# ac-adapter.net
KiCad netlist of a schematic drawn in EAGLE
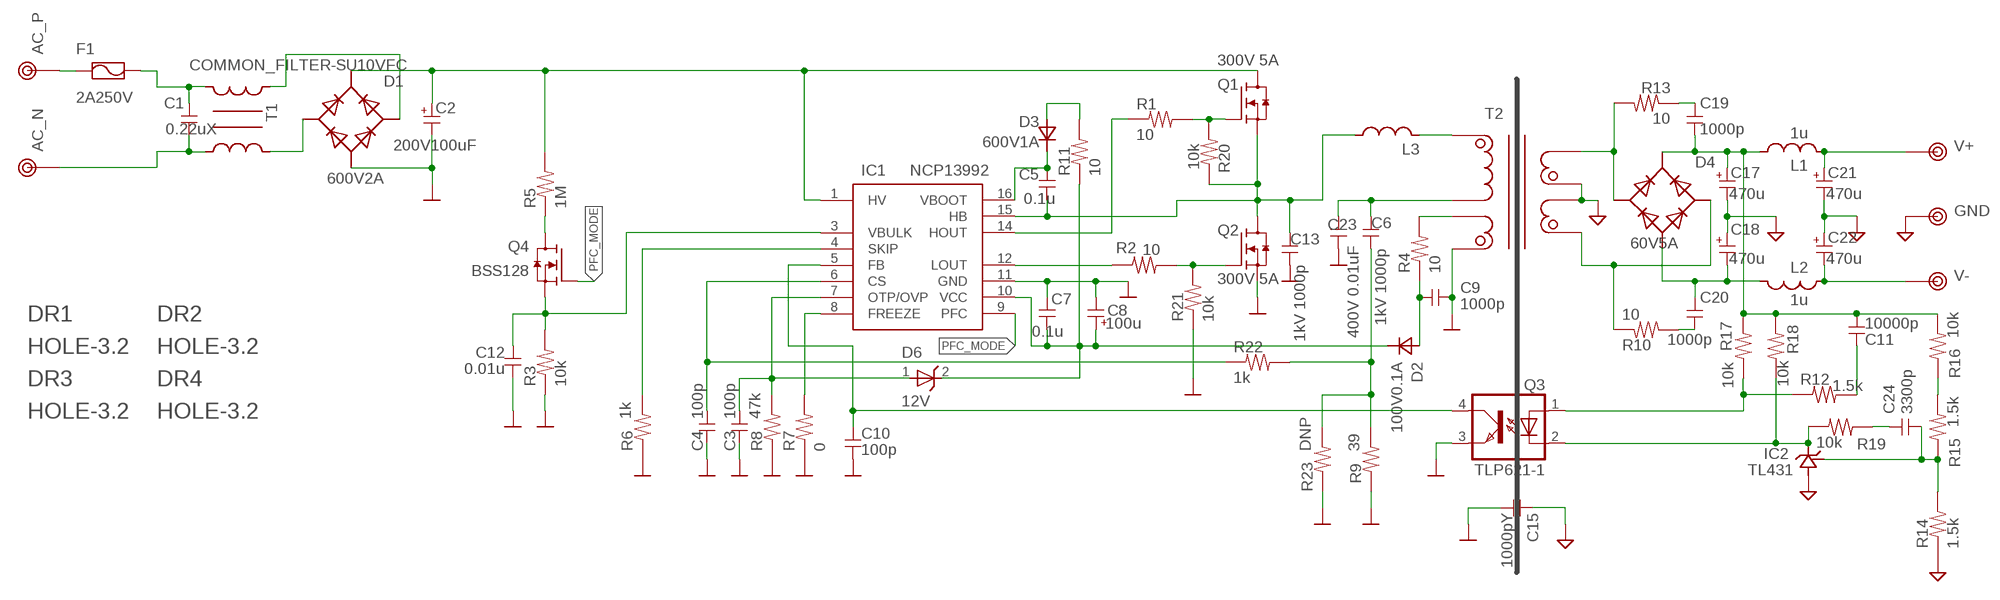
[diagram p0: schematic, sheet 1]

(export (version "E")
  (design (tool "Eeschema 10.0.6"))
  (components
    (comp (ref "C1")
      (value "0.22uX")
      (footprint "eagle-import:X-CAPACITER")
      (libsource (lib "eagle-import") (part "C-X"))
    )
    (comp (ref "C2")
      (value "200V100uF")
      (footprint "eagle-import:E5-16A2")
      (libsource (lib "eagle-import") (part "CPOLE7.5-16A2"))
    )
    (comp (ref "C3")
      (value "100p")
      (footprint "eagle-import:1608")
      (libsource (lib "eagle-import") (part "C-1608"))
    )
    (comp (ref "C4")
      (value "100p")
      (footprint "eagle-import:1608")
      (libsource (lib "eagle-import") (part "C-1608"))
    )
    (comp (ref "C5")
      (value "0.1u")
      (footprint "eagle-import:1608")
      (libsource (lib "eagle-import") (part "C-1608"))
    )
    (comp (ref "C6")
      (value "1kV 1000p")
      (footprint "eagle-import:C050")
      (libsource (lib "eagle-import") (part "C-5"))
    )
    (comp (ref "C7")
      (value "0.1u")
      (footprint "eagle-import:1608")
      (libsource (lib "eagle-import") (part "C-1608"))
    )
    (comp (ref "C8")
      (value "100u")
      (footprint "eagle-import:E2.5-6.5")
      (libsource (lib "eagle-import") (part "CPOLE2.5-6.5"))
    )
    (comp (ref "C9")
      (value "1000p")
      (footprint "eagle-import:1608")
      (libsource (lib "eagle-import") (part "C-1608"))
    )
    (comp (ref "C10")
      (value "100p")
      (footprint "eagle-import:1608")
      (libsource (lib "eagle-import") (part "C-1608"))
    )
    (comp (ref "C11")
      (value "10000p")
      (footprint "eagle-import:1608")
      (libsource (lib "eagle-import") (part "C-1608"))
    )
    (comp (ref "C12")
      (value "0.01u")
      (footprint "eagle-import:1608")
      (libsource (lib "eagle-import") (part "C-1608"))
    )
    (comp (ref "C13")
      (value "1kV 1000p")
      (footprint "eagle-import:C050")
      (libsource (lib "eagle-import") (part "C-5"))
    )
    (comp (ref "C15")
      (value "1000pY")
      (footprint "eagle-import:Y-CAPACITER")
      (libsource (lib "eagle-import") (part "C-Y"))
    )
    (comp (ref "C17")
      (value "470u")
      (footprint "eagle-import:E5-10")
      (libsource (lib "eagle-import") (part "CPOLE5-10"))
    )
    (comp (ref "C18")
      (value "470u")
      (footprint "eagle-import:E5-10")
      (libsource (lib "eagle-import") (part "CPOLE5-10"))
    )
    (comp (ref "C19")
      (value "1000p")
      (footprint "eagle-import:1608")
      (libsource (lib "eagle-import") (part "C-1608"))
    )
    (comp (ref "C20")
      (value "1000p")
      (footprint "eagle-import:1608")
      (libsource (lib "eagle-import") (part "C-1608"))
    )
    (comp (ref "C21")
      (value "470u")
      (footprint "eagle-import:E5-10")
      (libsource (lib "eagle-import") (part "CPOLE5-10"))
    )
    (comp (ref "C22")
      (value "470u")
      (footprint "eagle-import:E5-10")
      (libsource (lib "eagle-import") (part "CPOLE5-10"))
    )
    (comp (ref "C23")
      (value "400V 0.01uF")
      (footprint "eagle-import:C125")
      (libsource (lib "eagle-import") (part "C-12.5"))
    )
    (comp (ref "C24")
      (value "3300p")
      (footprint "eagle-import:1608")
      (libsource (lib "eagle-import") (part "C-1608"))
    )
    (comp (ref "D1")
      (value "600V2A")
      (footprint "eagle-import:GBU8A")
      (libsource (lib "eagle-import") (part "DIODE4-GBU8A"))
    )
    (comp (ref "D2")
      (value "100V0.1A")
      (footprint "eagle-import:SOD123")
      (libsource (lib "eagle-import") (part "DIODE-1N4148W"))
    )
    (comp (ref "D3")
      (value "600V1A")
      (footprint "eagle-import:D0204_7")
      (libsource (lib "eagle-import") (part "DIODE-7"))
    )
    (comp (ref "D4")
      (value "60V5A")
      (footprint "eagle-import:RBA-406")
      (libsource (lib "eagle-import") (part "DIODE4-RBA406B"))
    )
    (comp (ref "D6")
      (value "12V")
      (footprint "eagle-import:SOD123")
      (libsource (lib "eagle-import") (part "ZENER-SMD"))
    )
    (comp (ref "DR1")
      (value "HOLE-3.2")
      (footprint "eagle-import:HOLE_3.2")
      (libsource (lib "eagle-import") (part "HOLE-3.2"))
    )
    (comp (ref "DR2")
      (value "HOLE-3.2")
      (footprint "eagle-import:HOLE_3.2")
      (libsource (lib "eagle-import") (part "HOLE-3.2"))
    )
    (comp (ref "DR3")
      (value "HOLE-3.2")
      (footprint "eagle-import:HOLE_3.2")
      (libsource (lib "eagle-import") (part "HOLE-3.2"))
    )
    (comp (ref "DR4")
      (value "HOLE-3.2")
      (footprint "eagle-import:HOLE_3.2")
      (libsource (lib "eagle-import") (part "HOLE-3.2"))
    )
    (comp (ref "F1")
      (value "2A250V")
      (footprint "eagle-import:FUSE-5")
      (libsource (lib "eagle-import") (part "FUSE-5"))
    )
    (comp (ref "IC1")
      (value "NCP13992")
      (footprint "eagle-import:SO16-NCP13992")
      (libsource (lib "eagle-import") (part "NCP13992"))
    )
    (comp (ref "IC2")
      (value "TL431")
      (footprint "eagle-import:TO-92")
      (libsource (lib "eagle-import") (part "TL431"))
    )
    (comp (ref "L1")
      (value "1u")
      (footprint "eagle-import:L5-7,5")
      (libsource (lib "eagle-import") (part "L-5"))
    )
    (comp (ref "L2")
      (value "1u")
      (footprint "eagle-import:L5-7,5")
      (libsource (lib "eagle-import") (part "L-5"))
    )
    (comp (ref "L3")
      (value "L-PQ20")
      (footprint "eagle-import:BPQ20_20")
      (libsource (lib "eagle-import") (part "L-PQ20"))
    )
    (comp (ref "Q1")
      (value "300V 5A")
      (footprint "eagle-import:TO-220")
      (libsource (lib "eagle-import") (part "NMOS"))
    )
    (comp (ref "Q2")
      (value "300V 5A")
      (footprint "eagle-import:TO-220")
      (libsource (lib "eagle-import") (part "NMOS"))
    )
    (comp (ref "Q3")
      (value "TLP621-1")
      (footprint "eagle-import:DIL04")
      (libsource (lib "eagle-import") (part "TLP621-1"))
    )
    (comp (ref "Q4")
      (value "BSS128")
      (footprint "eagle-import:SC59")
      (libsource (lib "eagle-import") (part "NMOS-SMD"))
    )
    (comp (ref "R1")
      (value "10")
      (footprint "eagle-import:2012")
      (libsource (lib "eagle-import") (part "R-2012"))
    )
    (comp (ref "R2")
      (value "10")
      (footprint "eagle-import:2012")
      (libsource (lib "eagle-import") (part "R-2012"))
    )
    (comp (ref "R3")
      (value "10k")
      (footprint "eagle-import:1608")
      (libsource (lib "eagle-import") (part "R-1608"))
    )
    (comp (ref "R4")
      (value "10")
      (footprint "eagle-import:1608")
      (libsource (lib "eagle-import") (part "R-1608"))
    )
    (comp (ref "R5")
      (value "1M")
      (footprint "eagle-import:0204_7")
      (libsource (lib "eagle-import") (part "R-7.5"))
    )
    (comp (ref "R6")
      (value "1k")
      (footprint "eagle-import:1608")
      (libsource (lib "eagle-import") (part "R-1608"))
    )
    (comp (ref "R7")
      (value "0")
      (footprint "eagle-import:1608-J")
      (libsource (lib "eagle-import") (part "R-1608J"))
    )
    (comp (ref "R8")
      (value "47k")
      (footprint "eagle-import:1608")
      (libsource (lib "eagle-import") (part "R-1608"))
    )
    (comp (ref "R9")
      (value "39")
      (footprint "eagle-import:1608")
      (libsource (lib "eagle-import") (part "R-1608"))
    )
    (comp (ref "R10")
      (value "10")
      (footprint "eagle-import:2012")
      (libsource (lib "eagle-import") (part "R-2012"))
    )
    (comp (ref "R11")
      (value "10")
      (footprint "eagle-import:1608")
      (libsource (lib "eagle-import") (part "R-1608"))
    )
    (comp (ref "R12")
      (value "1.5k")
      (footprint "eagle-import:1608")
      (libsource (lib "eagle-import") (part "R-1608"))
    )
    (comp (ref "R13")
      (value "10")
      (footprint "eagle-import:2012")
      (libsource (lib "eagle-import") (part "R-2012"))
    )
    (comp (ref "R14")
      (value "1.5k")
      (footprint "eagle-import:1608")
      (libsource (lib "eagle-import") (part "R-1608"))
    )
    (comp (ref "R15")
      (value "1.5k")
      (footprint "eagle-import:1608")
      (libsource (lib "eagle-import") (part "R-1608"))
    )
    (comp (ref "R16")
      (value "10k")
      (footprint "eagle-import:1608")
      (libsource (lib "eagle-import") (part "R-1608"))
    )
    (comp (ref "R17")
      (value "10k")
      (footprint "eagle-import:1608")
      (libsource (lib "eagle-import") (part "R-1608"))
    )
    (comp (ref "R18")
      (value "10k")
      (footprint "eagle-import:1608")
      (libsource (lib "eagle-import") (part "R-1608"))
    )
    (comp (ref "R19")
      (value "10k")
      (footprint "eagle-import:1608")
      (libsource (lib "eagle-import") (part "R-1608"))
    )
    (comp (ref "R20")
      (value "10k")
      (footprint "eagle-import:1608")
      (libsource (lib "eagle-import") (part "R-1608"))
    )
    (comp (ref "R21")
      (value "10k")
      (footprint "eagle-import:1608")
      (libsource (lib "eagle-import") (part "R-1608"))
    )
    (comp (ref "R22")
      (value "1k")
      (footprint "eagle-import:1608")
      (libsource (lib "eagle-import") (part "R-1608"))
    )
    (comp (ref "R23")
      (value "DNP")
      (footprint "eagle-import:1608")
      (libsource (lib "eagle-import") (part "R-1608"))
    )
    (comp (ref "T1")
      (value "COMMON_FILTER-SU10VFC")
      (footprint "eagle-import:SU10VFC")
      (libsource (lib "eagle-import") (part "COMMON_FILTER-SU10VFC"))
    )
    (comp (ref "T2")
      (value "TRANSFORMAER_FLYBACK-PQ2620")
      (footprint "eagle-import:BPQ26_20-1112CPFR")
      (libsource (lib "eagle-import") (part "TRANSFORMAER_FLYBACK-PQ2620"))
    )
    (comp (ref "TP1")
      (value "AC_P")
      (footprint "eagle-import:TESTPIN-BIG")
      (libsource (lib "eagle-import") (part "TESTPIN-BIG"))
    )
    (comp (ref "TP2")
      (value "AC_N")
      (footprint "eagle-import:TESTPIN-BIG")
      (libsource (lib "eagle-import") (part "TESTPIN-BIG"))
    )
    (comp (ref "TP3")
      (value "V+")
      (footprint "eagle-import:TESTPIN-BIG")
      (libsource (lib "eagle-import") (part "TESTPIN-BIG"))
    )
    (comp (ref "TP4")
      (value "V-")
      (footprint "eagle-import:TESTPIN-BIG")
      (libsource (lib "eagle-import") (part "TESTPIN-BIG"))
    )
    (comp (ref "TP5")
      (value "GND")
      (footprint "eagle-import:TESTPIN-BIG")
      (libsource (lib "eagle-import") (part "TESTPIN-BIG"))
    )
  )
  (nets
    (net (code "1") (name "GND") (class "Default")
      (node (ref "C15") (pin "1") (pinfunction "1_1") (pintype "passive"))
      (node (ref "C17") (pin "-") (pinfunction "2_-") (pintype "passive"))
      (node (ref "C18") (pin "+") (pinfunction "1_+") (pintype "passive"))
      (node (ref "C21") (pin "-") (pinfunction "2_-") (pintype "passive"))
      (node (ref "C22") (pin "+") (pinfunction "1_+") (pintype "passive"))
      (node (ref "IC2") (pin "2") (pinfunction "GND_2") (pintype "bidirectional"))
      (node (ref "R14") (pin "1") (pinfunction "1_1") (pintype "passive"))
      (node (ref "T2") (pin "10") (pinfunction "L4_N_10") (pintype "passive"))
      (node (ref "T2") (pin "9") (pinfunction "L3_P_9") (pintype "passive"))
      (node (ref "TP5") (pin "1") (pinfunction "1_1") (pintype "passive"))
    )
    (net (code "2") (name "Net-(C1-Pad2)") (class "Default")
      (node (ref "C1") (pin "2") (pinfunction "2_2") (pintype "passive"))
      (node (ref "T1") (pin "3") (pinfunction "3_3") (pintype "passive"))
      (node (ref "TP2") (pin "1") (pinfunction "1_1") (pintype "passive"))
    )
    (net (code "3") (name "Net-(C2-1)") (class "Default")
      (node (ref "C2") (pin "+") (pinfunction "1_+") (pintype "passive"))
      (node (ref "D1") (pin "1") (pinfunction "V+_1") (pintype "passive"))
      (node (ref "IC1") (pin "1") (pinfunction "HV_1") (pintype "power_in"))
      (node (ref "Q1") (pin "2") (pinfunction "D_2") (pintype "passive"))
      (node (ref "R5") (pin "2") (pinfunction "2_2") (pintype "passive"))
    )
    (net (code "4") (name "Net-(C6-Pad2)") (class "Default")
      (node (ref "C6") (pin "2") (pinfunction "2_2") (pintype "passive"))
      (node (ref "R22") (pin "2") (pinfunction "2_2") (pintype "passive"))
      (node (ref "R23") (pin "2") (pinfunction "2_2") (pintype "passive"))
      (node (ref "R9") (pin "2") (pinfunction "2_2") (pintype "passive"))
    )
    (net (code "5") (name "Net-(C8-1)") (class "Default")
      (node (ref "C7") (pin "1") (pinfunction "1_1") (pintype "passive"))
      (node (ref "C8") (pin "+") (pinfunction "1_+") (pintype "passive"))
      (node (ref "D2") (pin "2") (pinfunction "K_2") (pintype "passive"))
      (node (ref "D6") (pin "2") (pinfunction "C_2") (pintype "bidirectional"))
      (node (ref "IC1") (pin "10") (pinfunction "VCC_10") (pintype "power_in"))
      (node (ref "R11") (pin "1") (pinfunction "1_1") (pintype "passive"))
    )
    (net (code "6") (name "Net-(C11-Pad1)") (class "Default")
      (node (ref "C11") (pin "1") (pinfunction "1_1") (pintype "passive"))
      (node (ref "R12") (pin "2") (pinfunction "2_2") (pintype "passive"))
    )
    (net (code "7") (name "Net-(C17-1)") (class "Default")
      (node (ref "C11") (pin "2") (pinfunction "2_2") (pintype "passive"))
      (node (ref "C17") (pin "+") (pinfunction "1_+") (pintype "passive"))
      (node (ref "C19") (pin "2") (pinfunction "2_2") (pintype "passive"))
      (node (ref "D4") (pin "1") (pinfunction "V+_1") (pintype "passive"))
      (node (ref "L1") (pin "2") (pinfunction "1_2") (pintype "passive"))
      (node (ref "R16") (pin "2") (pinfunction "2_2") (pintype "passive"))
      (node (ref "R17") (pin "1") (pinfunction "1_1") (pintype "passive"))
      (node (ref "R18") (pin "2") (pinfunction "2_2") (pintype "passive"))
    )
    (net (code "8") (name "Net-(C18-2)") (class "Default")
      (node (ref "C18") (pin "-") (pinfunction "2_-") (pintype "passive"))
      (node (ref "C20") (pin "1") (pinfunction "1_1") (pintype "passive"))
      (node (ref "D4") (pin "4") (pinfunction "V-_4") (pintype "passive"))
      (node (ref "L2") (pin "2") (pinfunction "1_2") (pintype "passive"))
    )
    (net (code "9") (name "Net-(C19-Pad1)") (class "Default")
      (node (ref "C19") (pin "1") (pinfunction "1_1") (pintype "passive"))
      (node (ref "R13") (pin "1") (pinfunction "1_1") (pintype "passive"))
    )
    (net (code "10") (name "Net-(C20-Pad2)") (class "Default")
      (node (ref "C20") (pin "2") (pinfunction "2_2") (pintype "passive"))
      (node (ref "R10") (pin "2") (pinfunction "2_2") (pintype "passive"))
    )
    (net (code "11") (name "Net-(C21-1)") (class "Default")
      (node (ref "C21") (pin "+") (pinfunction "1_+") (pintype "passive"))
      (node (ref "L1") (pin "1") (pinfunction "2_1") (pintype "passive"))
      (node (ref "TP3") (pin "1") (pinfunction "1_1") (pintype "passive"))
    )
    (net (code "12") (name "Net-(C22-2)") (class "Default")
      (node (ref "C22") (pin "-") (pinfunction "2_-") (pintype "passive"))
      (node (ref "L2") (pin "1") (pinfunction "2_1") (pintype "passive"))
      (node (ref "TP4") (pin "1") (pinfunction "1_1") (pintype "passive"))
    )
    (net (code "13") (name "Net-(C24-Pad1)") (class "Default")
      (node (ref "C24") (pin "1") (pinfunction "1_1") (pintype "passive"))
      (node (ref "R19") (pin "2") (pinfunction "2_2") (pintype "passive"))
    )
    (net (code "14") (name "Net-(D1-AC1)") (class "Default")
      (node (ref "D1") (pin "2") (pinfunction "AC1_2") (pintype "passive"))
      (node (ref "T1") (pin "4") (pinfunction "4_4") (pintype "passive"))
    )
    (net (code "15") (name "Net-(D1-AC2)") (class "Default")
      (node (ref "D1") (pin "3") (pinfunction "AC2_3") (pintype "passive"))
      (node (ref "T1") (pin "1") (pinfunction "1_1") (pintype "passive"))
    )
    (net (code "16") (name "Net-(D2-A)") (class "Default")
      (node (ref "C9") (pin "1") (pinfunction "1_1") (pintype "passive"))
      (node (ref "D2") (pin "1") (pinfunction "A_1") (pintype "passive"))
      (node (ref "R4") (pin "1") (pinfunction "1_1") (pintype "passive"))
    )
    (net (code "17") (name "Net-(D3-A)") (class "Default")
      (node (ref "D3") (pin "1") (pinfunction "A_1") (pintype "passive"))
      (node (ref "R11") (pin "2") (pinfunction "2_2") (pintype "passive"))
    )
    (net (code "18") (name "Net-(D3-K)") (class "Default")
      (node (ref "C5") (pin "1") (pinfunction "1_1") (pintype "passive"))
      (node (ref "D3") (pin "2") (pinfunction "K_2") (pintype "passive"))
      (node (ref "IC1") (pin "16") (pinfunction "VBOOT_16") (pintype "power_in"))
    )
    (net (code "19") (name "Net-(D4-AC1)") (class "Default")
      (node (ref "D4") (pin "2") (pinfunction "AC1_2") (pintype "passive"))
      (node (ref "R13") (pin "2") (pinfunction "2_2") (pintype "passive"))
      (node (ref "T2") (pin "7") (pinfunction "L3_N_7") (pintype "passive"))
      (node (ref "T2") (pin "8") (pinfunction "L3_N_8") (pintype "passive"))
    )
    (net (code "20") (name "Net-(D4-AC2)") (class "Default")
      (node (ref "D4") (pin "3") (pinfunction "AC2_3") (pintype "passive"))
      (node (ref "R10") (pin "1") (pinfunction "1_1") (pintype "passive"))
      (node (ref "T2") (pin "11") (pinfunction "L4_P_11") (pintype "passive"))
      (node (ref "T2") (pin "12") (pinfunction "L4_P_12") (pintype "passive"))
    )
    (net (code "21") (name "Net-(D6-A)") (class "Default")
      (node (ref "C3") (pin "1") (pinfunction "1_1") (pintype "passive"))
      (node (ref "D6") (pin "1") (pinfunction "A_1") (pintype "bidirectional"))
      (node (ref "IC1") (pin "7") (pinfunction "OTP/OVP_7") (pintype "bidirectional"))
      (node (ref "R8") (pin "2") (pinfunction "2_2") (pintype "passive"))
    )
    (net (code "22") (name "Net-(F1-P$1)") (class "Default")
      (node (ref "F1") (pin "1") (pinfunction "P$1_1") (pintype "passive"))
      (node (ref "TP1") (pin "1") (pinfunction "1_1") (pintype "passive"))
    )
    (net (code "23") (name "Net-(F1-P$2)") (class "Default")
      (node (ref "C1") (pin "1") (pinfunction "1_1") (pintype "passive"))
      (node (ref "F1") (pin "2") (pinfunction "P$2_2") (pintype "passive"))
      (node (ref "T1") (pin "2") (pinfunction "2_2") (pintype "passive"))
    )
    (net (code "24") (name "Net-(IC1-CS)") (class "Default")
      (node (ref "C4") (pin "1") (pinfunction "1_1") (pintype "passive"))
      (node (ref "IC1") (pin "6") (pinfunction "CS_6") (pintype "input"))
      (node (ref "R22") (pin "1") (pinfunction "1_1") (pintype "passive"))
    )
    (net (code "25") (name "Net-(IC1-FB)") (class "Default")
      (node (ref "C10") (pin "1") (pinfunction "1_1") (pintype "passive"))
      (node (ref "IC1") (pin "5") (pinfunction "FB_5") (pintype "input"))
      (node (ref "Q3") (pin "4") (pinfunction "COL_4") (pintype "passive"))
    )
    (net (code "26") (name "Net-(IC1-FREEZE)") (class "Default")
      (node (ref "IC1") (pin "8") (pinfunction "FREEZE_8") (pintype "bidirectional"))
      (node (ref "R7") (pin "2") (pinfunction "2_2") (pintype "passive"))
    )
    (net (code "27") (name "Net-(IC1-HB)") (class "Default")
      (node (ref "C13") (pin "1") (pinfunction "1_1") (pintype "passive"))
      (node (ref "C5") (pin "2") (pinfunction "2_2") (pintype "passive"))
      (node (ref "IC1") (pin "15") (pinfunction "HB_15") (pintype "power_in"))
      (node (ref "L3") (pin "4") (pinfunction "1_4") (pintype "passive"))
      (node (ref "Q1") (pin "3") (pinfunction "S_3") (pintype "passive"))
      (node (ref "Q2") (pin "2") (pinfunction "D_2") (pintype "passive"))
      (node (ref "R20") (pin "2") (pinfunction "2_2") (pintype "passive"))
    )
    (net (code "28") (name "Net-(IC1-HOUT)") (class "Default")
      (node (ref "IC1") (pin "14") (pinfunction "HOUT_14") (pintype "output"))
      (node (ref "R1") (pin "1") (pinfunction "1_1") (pintype "passive"))
    )
    (net (code "29") (name "Net-(IC1-LOUT)") (class "Default")
      (node (ref "IC1") (pin "12") (pinfunction "LOUT_12") (pintype "output"))
      (node (ref "R2") (pin "2") (pinfunction "2_2") (pintype "passive"))
    )
    (net (code "30") (name "Net-(IC1-SKIP)") (class "Default")
      (node (ref "IC1") (pin "4") (pinfunction "SKIP_4") (pintype "input"))
      (node (ref "R6") (pin "2") (pinfunction "2_2") (pintype "passive"))
    )
    (net (code "31") (name "Net-(IC1-VBULK)") (class "Default")
      (node (ref "C12") (pin "1") (pinfunction "1_1") (pintype "passive"))
      (node (ref "IC1") (pin "3") (pinfunction "VBULK_3") (pintype "input"))
      (node (ref "Q4") (pin "2") (pinfunction "S_2") (pintype "passive"))
      (node (ref "R3") (pin "2") (pinfunction "2_2") (pintype "passive"))
    )
    (net (code "32") (name "Net-(IC2-OUT)") (class "Default")
      (node (ref "IC2") (pin "3") (pinfunction "OUT_3") (pintype "bidirectional"))
      (node (ref "Q3") (pin "2") (pinfunction "C_2") (pintype "passive"))
      (node (ref "R18") (pin "1") (pinfunction "1_1") (pintype "passive"))
      (node (ref "R19") (pin "1") (pinfunction "1_1") (pintype "passive"))
    )
    (net (code "33") (name "Net-(IC2-REF)") (class "Default")
      (node (ref "C24") (pin "2") (pinfunction "2_2") (pintype "passive"))
      (node (ref "IC2") (pin "1") (pinfunction "REF_1") (pintype "input"))
      (node (ref "R14") (pin "2") (pinfunction "2_2") (pintype "passive"))
      (node (ref "R15") (pin "1") (pinfunction "1_1") (pintype "passive"))
    )
    (net (code "34") (name "Net-(L3-2)") (class "Default")
      (node (ref "L3") (pin "6") (pinfunction "2_6") (pintype "passive"))
      (node (ref "T2") (pin "1") (pinfunction "L1_P_1") (pintype "passive"))
    )
    (net (code "35") (name "Net-(Q1-G)") (class "Default")
      (node (ref "Q1") (pin "1") (pinfunction "G_1") (pintype "passive"))
      (node (ref "R1") (pin "2") (pinfunction "2_2") (pintype "passive"))
      (node (ref "R20") (pin "1") (pinfunction "1_1") (pintype "passive"))
    )
    (net (code "36") (name "Net-(Q2-G)") (class "Default")
      (node (ref "Q2") (pin "1") (pinfunction "G_1") (pintype "passive"))
      (node (ref "R2") (pin "1") (pinfunction "1_1") (pintype "passive"))
      (node (ref "R21") (pin "2") (pinfunction "2_2") (pintype "passive"))
    )
    (net (code "37") (name "Net-(Q3-A)") (class "Default")
      (node (ref "Q3") (pin "1") (pinfunction "A_1") (pintype "passive"))
      (node (ref "R12") (pin "1") (pinfunction "1_1") (pintype "passive"))
      (node (ref "R17") (pin "2") (pinfunction "2_2") (pintype "passive"))
    )
    (net (code "38") (name "Net-(Q4-D)") (class "Default")
      (node (ref "Q4") (pin "3") (pinfunction "D_3") (pintype "passive"))
      (node (ref "R5") (pin "1") (pinfunction "1_1") (pintype "passive"))
    )
    (net (code "39") (name "Net-(R15-Pad2)") (class "Default")
      (node (ref "R15") (pin "2") (pinfunction "2_2") (pintype "passive"))
      (node (ref "R16") (pin "1") (pinfunction "1_1") (pintype "passive"))
    )
    (net (code "40") (name "Net-(T2-L1_N)") (class "Default")
      (node (ref "C23") (pin "1") (pinfunction "1_1") (pintype "passive"))
      (node (ref "C6") (pin "1") (pinfunction "1_1") (pintype "passive"))
      (node (ref "T2") (pin "3") (pinfunction "L1_N_3") (pintype "passive"))
    )
    (net (code "41") (name "Net-(T2-L2_N)") (class "Default")
      (node (ref "R4") (pin "2") (pinfunction "2_2") (pintype "passive"))
      (node (ref "T2") (pin "6") (pinfunction "L2_N_6") (pintype "passive"))
    )
    (net (code "42") (name "PFC_MODE") (class "Default")
      (node (ref "IC1") (pin "9") (pinfunction "PFC_9") (pintype "output"))
      (node (ref "Q4") (pin "1") (pinfunction "G_1") (pintype "passive"))
    )
    (net (code "43") (name "PGND") (class "Default")
      (node (ref "C10") (pin "2") (pinfunction "2_2") (pintype "passive"))
      (node (ref "C12") (pin "2") (pinfunction "2_2") (pintype "passive"))
      (node (ref "C13") (pin "2") (pinfunction "2_2") (pintype "passive"))
      (node (ref "C15") (pin "2") (pinfunction "2_2") (pintype "passive"))
      (node (ref "C2") (pin "-") (pinfunction "2_-") (pintype "passive"))
      (node (ref "C23") (pin "2") (pinfunction "2_2") (pintype "passive"))
      (node (ref "C3") (pin "2") (pinfunction "2_2") (pintype "passive"))
      (node (ref "C4") (pin "2") (pinfunction "2_2") (pintype "passive"))
      (node (ref "C7") (pin "2") (pinfunction "2_2") (pintype "passive"))
      (node (ref "C8") (pin "-") (pinfunction "2_-") (pintype "passive"))
      (node (ref "C9") (pin "2") (pinfunction "2_2") (pintype "passive"))
      (node (ref "D1") (pin "4") (pinfunction "V-_4") (pintype "passive"))
      (node (ref "IC1") (pin "11") (pinfunction "GND_11") (pintype "power_in"))
      (node (ref "Q2") (pin "3") (pinfunction "S_3") (pintype "passive"))
      (node (ref "Q3") (pin "3") (pinfunction "EMIT_3") (pintype "passive"))
      (node (ref "R21") (pin "1") (pinfunction "1_1") (pintype "passive"))
      (node (ref "R23") (pin "1") (pinfunction "1_1") (pintype "passive"))
      (node (ref "R3") (pin "1") (pinfunction "1_1") (pintype "passive"))
      (node (ref "R6") (pin "1") (pinfunction "1_1") (pintype "passive"))
      (node (ref "R7") (pin "1") (pinfunction "1_1") (pintype "passive"))
      (node (ref "R8") (pin "1") (pinfunction "1_1") (pintype "passive"))
      (node (ref "R9") (pin "1") (pinfunction "1_1") (pintype "passive"))
      (node (ref "T2") (pin "5") (pinfunction "L2_P_5") (pintype "passive"))
    )
  )
)
